# PressureSensor.net
KiCad netlist of a schematic drawn in Altium Designer
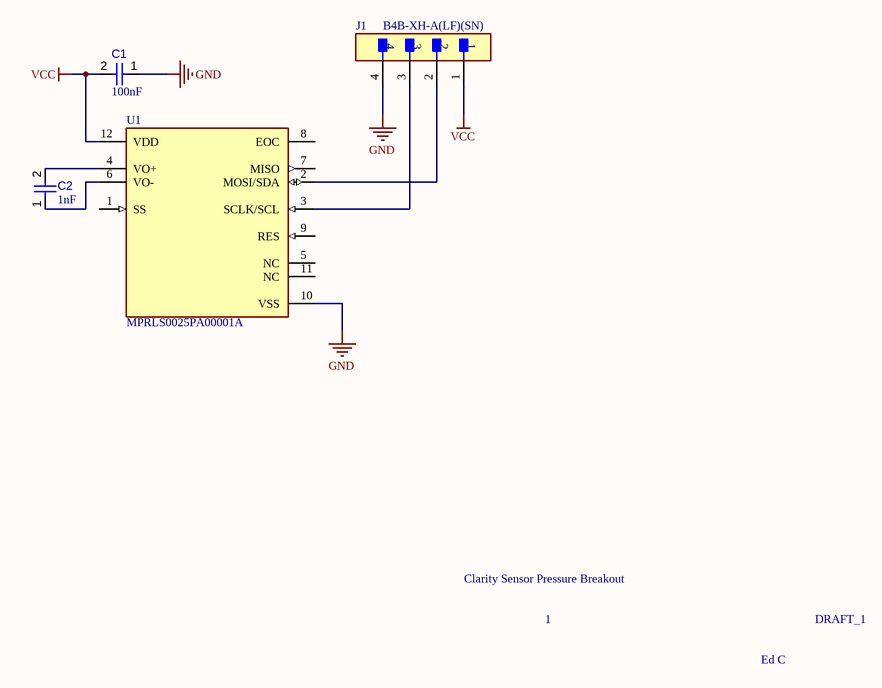
[diagram p0: PressureSensor.SchDoc]

(export (version "E")
  (design (tool "Eeschema 10.0.6"))
  (components
    (comp (ref "C1")
      (value "100nF")
      (footprint "CAPC1608X90X40NL10T20")
      (description "Chip Capacitor, 100 nF, +/- 10%, 50 V, 0603 (1608 Metric)")
      (fields (field (name "TOLERANCE") "10%") (field (name "Comment") "Capacitor 100 nF +/-10% 50 V 0603"))
      (libsource (lib "University of Auckland") (part "CAP-NP-2"))
    )
    (comp (ref "C2")
      (value "1nF")
      (footprint "FP-0603-L_1_6_0_15-W_0_81-IPC_C")
      (fields (field (name "Comment") "06035C102KAT2A"))
      (libsource (lib "University of Auckland") (part "CAP-NP-2"))
    )
    (comp (ref "J1")
      (value "B4B-XH-A(LF)(SN)")
      (footprint "FP-B4B-XH-A_LF_SN-MFG")
      (description "Header for PCB; pitch 2.50mm; 4-contacts; THT male; top entry; 250V/3A")
      (libsource (lib "University of Auckland") (part "299a8cea1bdcbc3624fe62c390fa72c"))
    )
    (comp (ref "U1")
      (value "MPRLS0025PA00001A")
      (footprint "FP-MPRLS0025PA00001A-MFG")
      (description "Absolute, 0Psi Min, 25Psi Max, 0.25%, 0.20-0.80V, Square, Board Mount")
      (libsource (lib "University of Auckland") (part "5f5de855ae9f64f142a9fe0697e183a"))
    )
  )
  (nets
    (net (code "1") (name "GND") (class "Default")
      (node (ref "C1") (pin "1") (pinfunction "1_1") (pintype "passive"))
      (node (ref "J1") (pin "4") (pinfunction "4_4") (pintype "passive"))
      (node (ref "U1") (pin "10") (pinfunction "VSS_10") (pintype "power_in"))
    )
    (net (code "2") (name "Net-(U1-MOSI{slash}SDA)") (class "Default")
      (node (ref "J1") (pin "2") (pinfunction "2_2") (pintype "passive"))
      (node (ref "U1") (pin "2") (pinfunction "MOSI/SDA_2") (pintype "bidirectional"))
    )
    (net (code "3") (name "Net-(U1-SCLK{slash}SCL)") (class "Default")
      (node (ref "J1") (pin "3") (pinfunction "3_3") (pintype "passive"))
      (node (ref "U1") (pin "3") (pinfunction "SCLK/SCL_3") (pintype "input"))
    )
    (net (code "4") (name "Net-(U1-VO+)") (class "Default")
      (node (ref "C2") (pin "2") (pinfunction "2_2") (pintype "passive"))
      (node (ref "U1") (pin "4") (pinfunction "VO+_4") (pintype "power_in"))
    )
    (net (code "5") (name "Net-(U1-VO-)") (class "Default")
      (node (ref "C2") (pin "1") (pinfunction "1_1") (pintype "passive"))
      (node (ref "U1") (pin "6") (pinfunction "VO-_6") (pintype "power_in"))
    )
    (net (code "6") (name "VCC") (class "Default")
      (node (ref "C1") (pin "2") (pinfunction "2_2") (pintype "passive"))
      (node (ref "J1") (pin "1") (pinfunction "1_1") (pintype "passive"))
      (node (ref "U1") (pin "12") (pinfunction "VDD_12") (pintype "power_in"))
    )
    (net (code "7") (name "unconnected-(U1-EOC-Pad8)") (class "Default")
      (node (ref "U1") (pin "8") (pinfunction "EOC_8") (pintype "passive"))
    )
    (net (code "8") (name "unconnected-(U1-MISO-Pad7)") (class "Default")
      (node (ref "U1") (pin "7") (pinfunction "MISO_7") (pintype "output"))
    )
    (net (code "9") (name "unconnected-(U1-NC-Pad5)") (class "Default")
      (node (ref "U1") (pin "5") (pinfunction "NC_5") (pintype "passive"))
    )
    (net (code "10") (name "unconnected-(U1-NC-Pad11)") (class "Default")
      (node (ref "U1") (pin "11") (pinfunction "NC_11") (pintype "passive"))
    )
    (net (code "11") (name "unconnected-(U1-RES-Pad9)") (class "Default")
      (node (ref "U1") (pin "9") (pinfunction "RES_9") (pintype "input"))
    )
    (net (code "12") (name "unconnected-(U1-SS-Pad1)") (class "Default")
      (node (ref "U1") (pin "1") (pinfunction "SS_1") (pintype "input"))
    )
  )
)
